# STB_LightBoard.net
KiCad netlist of a schematic drawn in Altium Designer
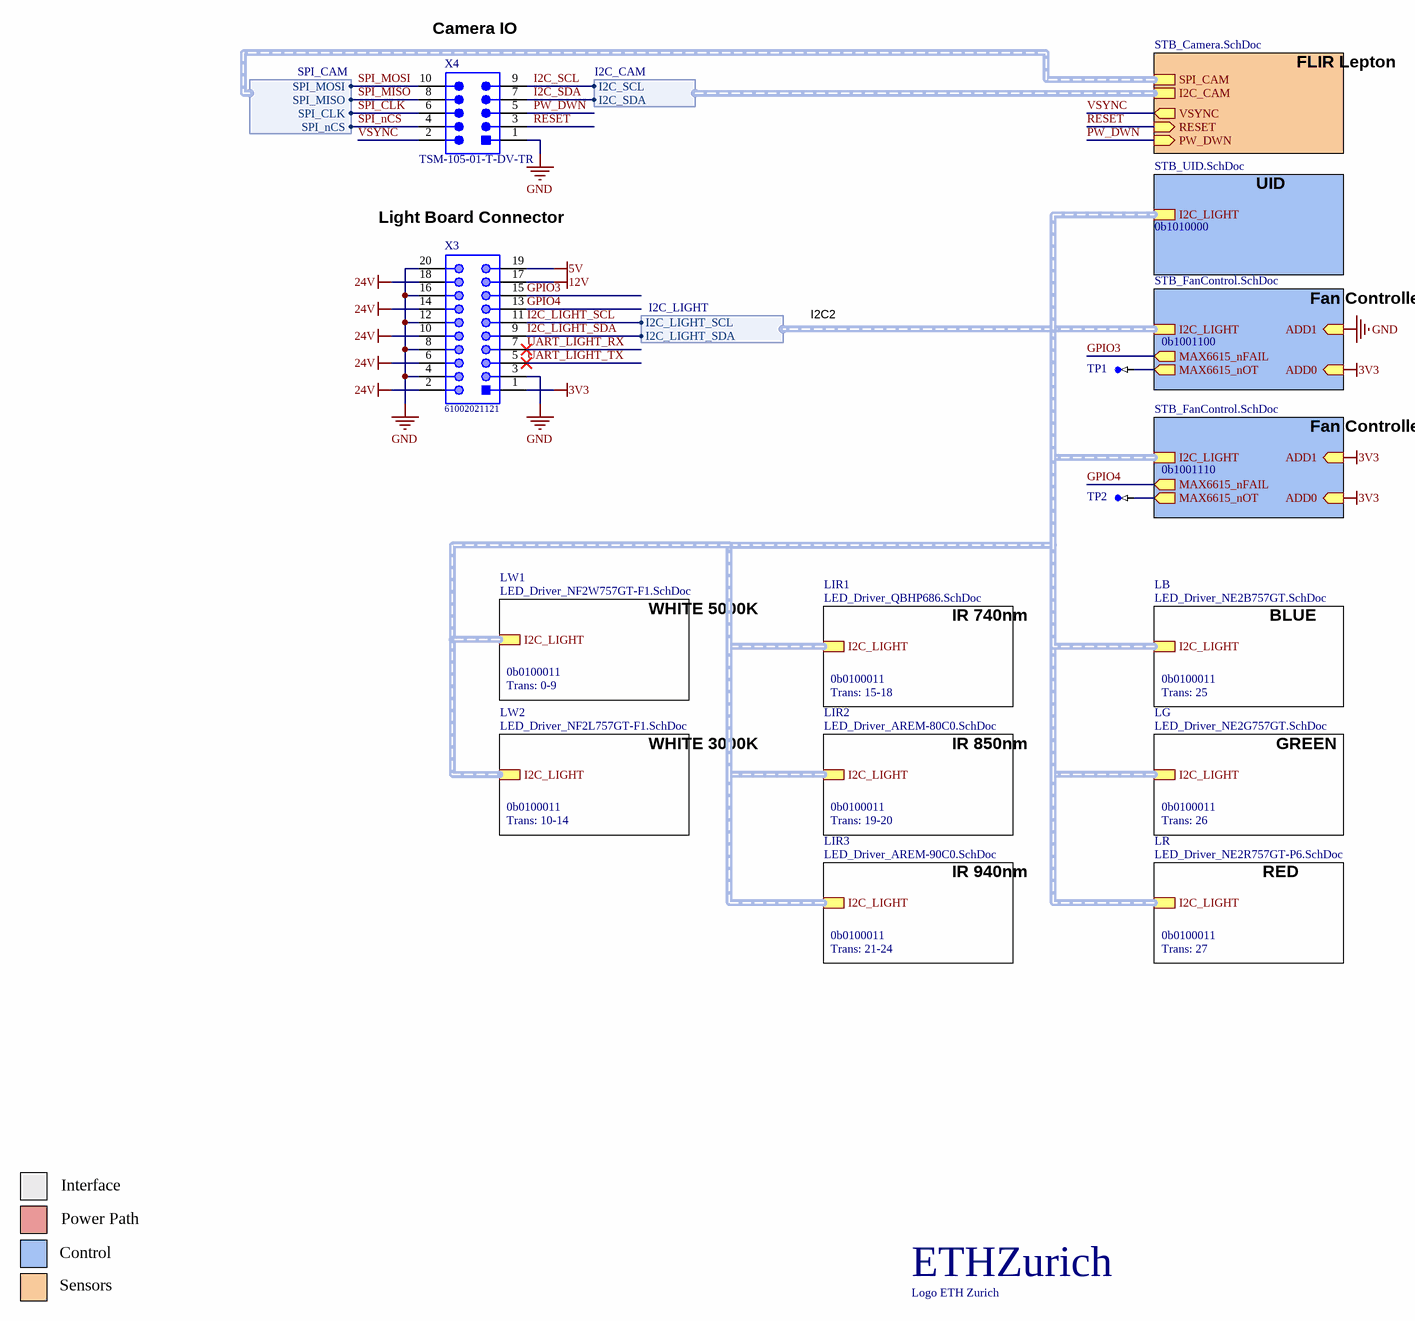
[diagram p0: STB_LightBoard.SchDoc]

(export (version "E")
  (design (tool "Eeschema 10.0.6"))
  (components
    (comp (ref "A1")
      (value "Logo ETH Zurich")
      (footprint "eth-zurich_5mm")
      (libsource (lib "ETHZ Vault") (part "Logo ETH Zurich"))
    )
    (comp (ref "TP1")
      (value "testPoint_1mm")
      (footprint "TP-SM-C-100")
      (description "testPoint 1mm")
      (libsource (lib "STB_Schlib") (part "testPoint_1mm"))
    )
    (comp (ref "TP2")
      (value "testPoint_1mm")
      (footprint "TP-SM-C-100")
      (description "testPoint 1mm")
      (libsource (lib "STB_Schlib") (part "testPoint_1mm"))
    )
    (comp (ref "X3")
      (value "61002021121")
      (footprint "61002021121")
      (description "SMT Vertical Pin Header WR-PHD, Pitch 2.54 mm, Dual Row, 20 pins")
      (fields (field (name "MANUFACTURER") "Wurth Elektronik") (field (name "PUBLISHER") "WurthElektronik"))
      (libsource (lib "Altium Content Vault") (part "WE-CN-2P-M-R20"))
    )
    (comp (ref "X4")
      (value "TSM-105-01-T-DV-TR")
      (footprint "SMTC-TSM-105-01-T-DV_V")
      (description "Male Header, Pitch 2.54 mm, 2 x 5 Position, Height 9.65 mm, -55 to 105 degC, RoHS, Tape and Reel")
      (fields (field (name "MANUFACTURER") "Samtec"))
      (libsource (lib "Altium Content Vault") (part "CN-2P-M-R10"))
    )
  )
  (nets
    (net (code "4") (name "/GPIO3") (class "Default")
      (node (ref "X3") (pin "15") (pinfunction "15_15") (pintype "passive"))
    )
    (net (code "5") (name "/GPIO4") (class "Default")
      (node (ref "X3") (pin "13") (pinfunction "13_13") (pintype "passive"))
    )
    (net (code "6") (name "/I2C_LIGHT_SCL") (class "Default")
      (node (ref "X3") (pin "11") (pinfunction "11_11") (pintype "passive"))
    )
    (net (code "7") (name "/I2C_LIGHT_SDA") (class "Default")
      (node (ref "X3") (pin "9") (pinfunction "9_9") (pintype "passive"))
    )
    (net (code "8") (name "/I2C_SCL") (class "Default")
      (node (ref "X4") (pin "9") (pinfunction "9_9") (pintype "passive"))
    )
    (net (code "9") (name "/I2C_SDA") (class "Default")
      (node (ref "X4") (pin "7") (pinfunction "7_7") (pintype "passive"))
    )
    (net (code "10") (name "/MAX6615_nOT") (class "Default")
      (node (ref "TP2") (pin "TP") (pinfunction "TP_TP") (pintype "input"))
    )
    (net (code "11") (name "/MAX6615_nOT_1") (class "Default")
      (node (ref "TP1") (pin "TP") (pinfunction "TP_TP") (pintype "input"))
    )
    (net (code "12") (name "/PW_DWN") (class "Default")
      (node (ref "X4") (pin "5") (pinfunction "5_5") (pintype "passive"))
    )
    (net (code "13") (name "/RESET") (class "Default")
      (node (ref "X4") (pin "3") (pinfunction "3_3") (pintype "passive"))
    )
    (net (code "14") (name "/SPI_CLK") (class "Default")
      (node (ref "X4") (pin "6") (pinfunction "6_6") (pintype "passive"))
    )
    (net (code "15") (name "/SPI_MISO") (class "Default")
      (node (ref "X4") (pin "8") (pinfunction "8_8") (pintype "passive"))
    )
    (net (code "16") (name "/SPI_MOSI") (class "Default")
      (node (ref "X4") (pin "10") (pinfunction "10_10") (pintype "passive"))
    )
    (net (code "17") (name "/SPI_nCS") (class "Default")
      (node (ref "X4") (pin "4") (pinfunction "4_4") (pintype "passive"))
    )
    (net (code "18") (name "/UART_LIGHT_RX") (class "Default")
      (node (ref "X3") (pin "7") (pinfunction "7_7") (pintype "passive+no_connect"))
    )
    (net (code "19") (name "/UART_LIGHT_TX") (class "Default")
      (node (ref "X3") (pin "5") (pinfunction "5_5") (pintype "passive+no_connect"))
    )
    (net (code "20") (name "/VSYNC") (class "Default")
      (node (ref "X4") (pin "2") (pinfunction "2_2") (pintype "passive"))
    )
    (net (code "24") (name "3V3") (class "Default")
      (node (ref "X3") (pin "1") (pinfunction "1_1") (pintype "passive"))
    )
    (net (code "25") (name "5V") (class "Default")
      (node (ref "X3") (pin "19") (pinfunction "19_19") (pintype "passive"))
    )
    (net (code "26") (name "12V") (class "Default")
      (node (ref "X3") (pin "17") (pinfunction "17_17") (pintype "passive"))
    )
    (net (code "27") (name "24V") (class "Default")
      (node (ref "X3") (pin "10") (pinfunction "10_10") (pintype "passive"))
      (node (ref "X3") (pin "14") (pinfunction "14_14") (pintype "passive"))
      (node (ref "X3") (pin "18") (pinfunction "18_18") (pintype "passive"))
      (node (ref "X3") (pin "2") (pinfunction "2_2") (pintype "passive"))
      (node (ref "X3") (pin "6") (pinfunction "6_6") (pintype "passive"))
    )
    (net (code "28") (name "GND") (class "Default")
      (node (ref "X3") (pin "12") (pinfunction "12_12") (pintype "passive"))
      (node (ref "X3") (pin "16") (pinfunction "16_16") (pintype "passive"))
      (node (ref "X3") (pin "20") (pinfunction "20_20") (pintype "passive"))
      (node (ref "X3") (pin "3") (pinfunction "3_3") (pintype "passive"))
      (node (ref "X3") (pin "4") (pinfunction "4_4") (pintype "passive"))
      (node (ref "X3") (pin "8") (pinfunction "8_8") (pintype "passive"))
      (node (ref "X4") (pin "1") (pinfunction "1_1") (pintype "passive"))
    )
  )
)
